# usb-power-maker.net
KiCad netlist of a schematic drawn in EAGLE
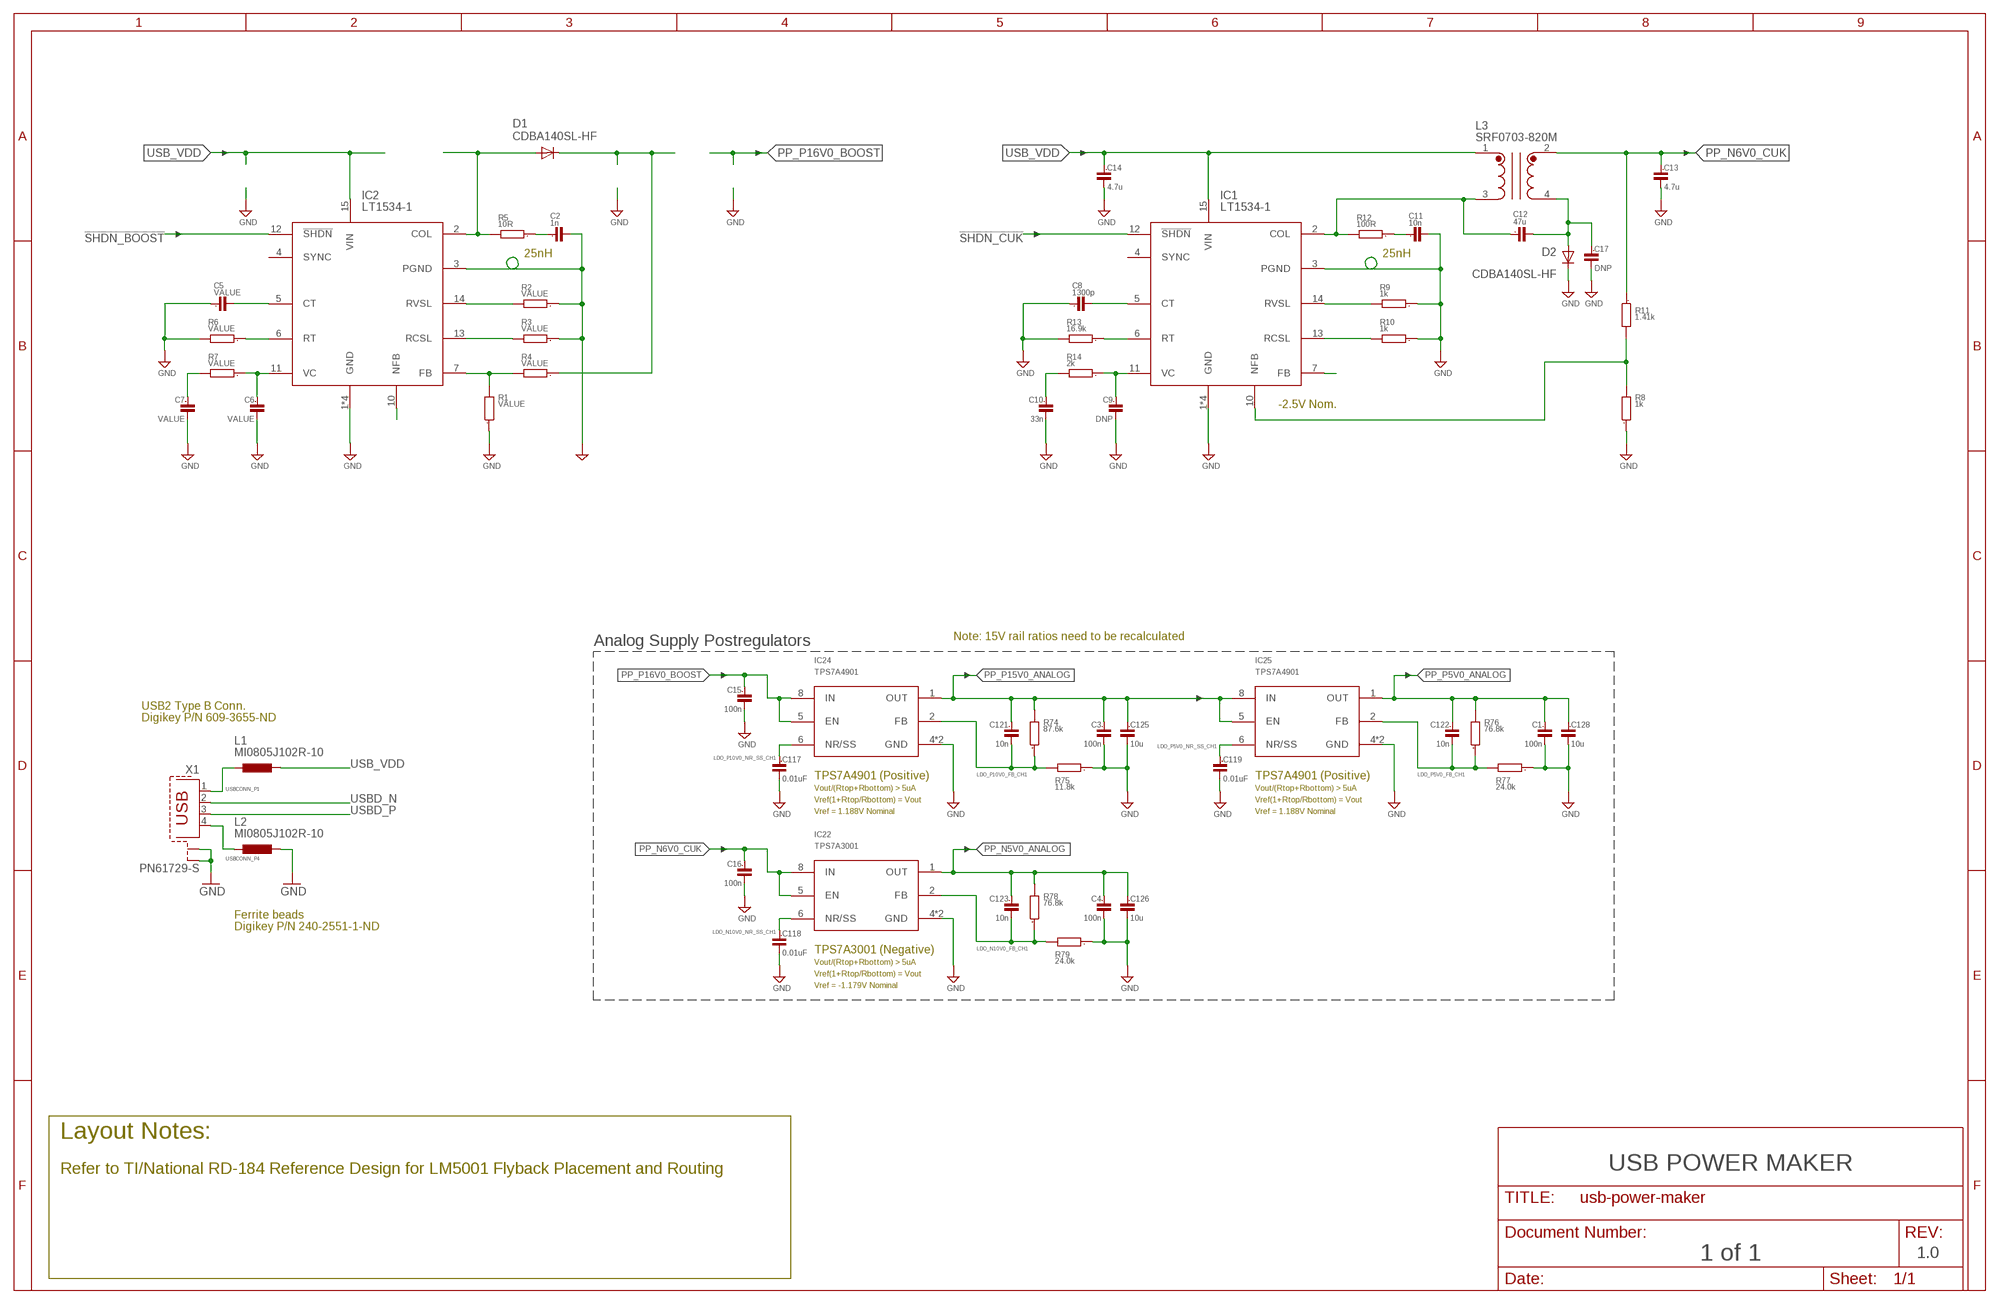
[diagram p0: schematic, sheet 1]

(export (version "E")
  (design (tool "Eeschema 10.0.6"))
  (components
    (comp (ref "C1")
      (value "100n")
      (footprint "eagle-import:0603")
      (libsource (lib "eagle-import") (part "C0603"))
    )
    (comp (ref "C2")
      (value "1n")
      (footprint "eagle-import:0603")
      (libsource (lib "eagle-import") (part "C0603"))
    )
    (comp (ref "C3")
      (value "100n")
      (footprint "eagle-import:0603")
      (libsource (lib "eagle-import") (part "C0603"))
    )
    (comp (ref "C4")
      (value "100n")
      (footprint "eagle-import:0603")
      (libsource (lib "eagle-import") (part "C0603"))
    )
    (comp (ref "C5")
      (value "VALUE")
      (footprint "eagle-import:0603")
      (libsource (lib "eagle-import") (part "C0603"))
    )
    (comp (ref "C6")
      (value "VALUE")
      (footprint "eagle-import:0603")
      (libsource (lib "eagle-import") (part "C0603"))
    )
    (comp (ref "C7")
      (value "VALUE")
      (footprint "eagle-import:0603")
      (libsource (lib "eagle-import") (part "C0603"))
    )
    (comp (ref "C8")
      (value "1300p")
      (footprint "eagle-import:0603")
      (libsource (lib "eagle-import") (part "C0603"))
    )
    (comp (ref "C9")
      (value "DNP")
      (footprint "eagle-import:0603")
      (libsource (lib "eagle-import") (part "C0603"))
    )
    (comp (ref "C10")
      (value "33n")
      (footprint "eagle-import:0603")
      (libsource (lib "eagle-import") (part "C0603"))
    )
    (comp (ref "C11")
      (value "10n")
      (footprint "eagle-import:0603")
      (libsource (lib "eagle-import") (part "C0603"))
    )
    (comp (ref "C12")
      (value "47u")
      (footprint "eagle-import:0805")
      (libsource (lib "eagle-import") (part "C0805"))
    )
    (comp (ref "C13")
      (value "4.7u")
      (footprint "eagle-import:0805")
      (libsource (lib "eagle-import") (part "C0805"))
    )
    (comp (ref "C14")
      (value "4.7u")
      (footprint "eagle-import:0805")
      (libsource (lib "eagle-import") (part "C0805"))
    )
    (comp (ref "C15")
      (value "100n")
      (footprint "eagle-import:0603")
      (libsource (lib "eagle-import") (part "C0603"))
    )
    (comp (ref "C16")
      (value "100n")
      (footprint "eagle-import:0603")
      (libsource (lib "eagle-import") (part "C0603"))
    )
    (comp (ref "C17")
      (value "DNP")
      (footprint "eagle-import:0603")
      (libsource (lib "eagle-import") (part "C0603"))
    )
    (comp (ref "C117")
      (value "0.01uF")
      (footprint "eagle-import:0603")
      (libsource (lib "eagle-import") (part "C0603"))
    )
    (comp (ref "C118")
      (value "0.01uF")
      (footprint "eagle-import:0603")
      (libsource (lib "eagle-import") (part "C0603"))
    )
    (comp (ref "C119")
      (value "0.01uF")
      (footprint "eagle-import:0603")
      (libsource (lib "eagle-import") (part "C0603"))
    )
    (comp (ref "C121")
      (value "10n")
      (footprint "eagle-import:0603")
      (libsource (lib "eagle-import") (part "C0603"))
    )
    (comp (ref "C122")
      (value "10n")
      (footprint "eagle-import:0603")
      (libsource (lib "eagle-import") (part "C0603"))
    )
    (comp (ref "C123")
      (value "10n")
      (footprint "eagle-import:0603")
      (libsource (lib "eagle-import") (part "C0603"))
    )
    (comp (ref "C125")
      (value "10u")
      (footprint "eagle-import:0805")
      (libsource (lib "eagle-import") (part "C0805"))
    )
    (comp (ref "C126")
      (value "10u")
      (footprint "eagle-import:0805")
      (libsource (lib "eagle-import") (part "C0805"))
    )
    (comp (ref "C128")
      (value "10u")
      (footprint "eagle-import:0805")
      (libsource (lib "eagle-import") (part "C0805"))
    )
    (comp (ref "D1")
      (value "CDBA140SL-HF")
      (footprint "eagle-import:DO214AC")
      (libsource (lib "eagle-import") (part "DIODE-DO214AC"))
    )
    (comp (ref "D2")
      (value "CDBA140SL-HF")
      (footprint "eagle-import:DO214AC")
      (libsource (lib "eagle-import") (part "DIODE-DO214AC"))
    )
    (comp (ref "IC1")
      (value "LT1534-1")
      (footprint "eagle-import:SO16")
      (libsource (lib "eagle-import") (part "LT1534"))
    )
    (comp (ref "IC2")
      (value "LT1534-1")
      (footprint "eagle-import:SO16")
      (libsource (lib "eagle-import") (part "LT1534"))
    )
    (comp (ref "IC22")
      (value "TPS7A3001")
      (footprint "eagle-import:MSOP-8_POWER_PAD")
      (libsource (lib "eagle-import") (part "TPS7A"))
    )
    (comp (ref "IC24")
      (value "TPS7A4901")
      (footprint "eagle-import:MSOP-8_POWER_PAD")
      (libsource (lib "eagle-import") (part "TPS7A"))
    )
    (comp (ref "IC25")
      (value "TPS7A4901")
      (footprint "eagle-import:MSOP-8_POWER_PAD")
      (libsource (lib "eagle-import") (part "TPS7A"))
    )
    (comp (ref "L1")
      (value "MI0805J102R-10")
      (footprint "eagle-import:R0805")
      (libsource (lib "eagle-import") (part "INDUCTOR0805"))
    )
    (comp (ref "L2")
      (value "MI0805J102R-10")
      (footprint "eagle-import:R0805")
      (libsource (lib "eagle-import") (part "INDUCTOR0805"))
    )
    (comp (ref "L3")
      (value "SRF0703-820M")
      (footprint "eagle-import:SRF0703")
      (libsource (lib "eagle-import") (part "SRF0703"))
    )
    (comp (ref "R1")
      (value "VALUE")
      (footprint "eagle-import:0603")
      (libsource (lib "eagle-import") (part "R0603"))
    )
    (comp (ref "R2")
      (value "VALUE")
      (footprint "eagle-import:0603")
      (libsource (lib "eagle-import") (part "R0603"))
    )
    (comp (ref "R3")
      (value "VALUE")
      (footprint "eagle-import:0603")
      (libsource (lib "eagle-import") (part "R0603"))
    )
    (comp (ref "R4")
      (value "VALUE")
      (footprint "eagle-import:0603")
      (libsource (lib "eagle-import") (part "R0603"))
    )
    (comp (ref "R5")
      (value "10R")
      (footprint "eagle-import:0603")
      (libsource (lib "eagle-import") (part "R0603"))
    )
    (comp (ref "R6")
      (value "VALUE")
      (footprint "eagle-import:0603")
      (libsource (lib "eagle-import") (part "R0603"))
    )
    (comp (ref "R7")
      (value "VALUE")
      (footprint "eagle-import:0603")
      (libsource (lib "eagle-import") (part "R0603"))
    )
    (comp (ref "R8")
      (value "1k")
      (footprint "eagle-import:0603")
      (libsource (lib "eagle-import") (part "R0603"))
    )
    (comp (ref "R9")
      (value "1k")
      (footprint "eagle-import:0603")
      (libsource (lib "eagle-import") (part "R0603"))
    )
    (comp (ref "R10")
      (value "1k")
      (footprint "eagle-import:0603")
      (libsource (lib "eagle-import") (part "R0603"))
    )
    (comp (ref "R11")
      (value "1.41k")
      (footprint "eagle-import:0603")
      (libsource (lib "eagle-import") (part "R0603"))
    )
    (comp (ref "R12")
      (value "100R")
      (footprint "eagle-import:0603")
      (libsource (lib "eagle-import") (part "R0603"))
    )
    (comp (ref "R13")
      (value "16.9k")
      (footprint "eagle-import:0603")
      (libsource (lib "eagle-import") (part "R0603"))
    )
    (comp (ref "R14")
      (value "2k")
      (footprint "eagle-import:0603")
      (libsource (lib "eagle-import") (part "R0603"))
    )
    (comp (ref "R74")
      (value "87.6k")
      (footprint "eagle-import:0603")
      (libsource (lib "eagle-import") (part "R0603"))
    )
    (comp (ref "R75")
      (value "11.8k")
      (footprint "eagle-import:0603")
      (libsource (lib "eagle-import") (part "R0603"))
    )
    (comp (ref "R76")
      (value "76.8k")
      (footprint "eagle-import:0603")
      (libsource (lib "eagle-import") (part "R0603"))
    )
    (comp (ref "R77")
      (value "24.0k")
      (footprint "eagle-import:0603")
      (libsource (lib "eagle-import") (part "R0603"))
    )
    (comp (ref "R78")
      (value "76.8k")
      (footprint "eagle-import:0603")
      (libsource (lib "eagle-import") (part "R0603"))
    )
    (comp (ref "R79")
      (value "24.0k")
      (footprint "eagle-import:0603")
      (libsource (lib "eagle-import") (part "R0603"))
    )
    (comp (ref "X1")
      (value "PN61729-S")
      (footprint "eagle-import:PN61729-S")
      (libsource (lib "eagle-import") (part "PN61729-S"))
    )
  )
  (nets
    (net (code "1") (name "/LDO_N10V0_FB_CH1") (class "Default")
      (node (ref "C123") (pin "2") (pinfunction "2_2") (pintype "passive"))
      (node (ref "IC22") (pin "2") (pinfunction "FB_2") (pintype "bidirectional"))
      (node (ref "R78") (pin "1") (pinfunction "1_1") (pintype "passive"))
      (node (ref "R79") (pin "2") (pinfunction "2_2") (pintype "passive"))
    )
    (net (code "2") (name "/LDO_N10V0_NR_SS_CH1") (class "Default")
      (node (ref "C118") (pin "1") (pinfunction "1_1") (pintype "passive"))
      (node (ref "IC22") (pin "6") (pinfunction "NR/SS_6") (pintype "bidirectional"))
    )
    (net (code "3") (name "/LDO_P5V0_FB_CH1") (class "Default")
      (node (ref "C122") (pin "2") (pinfunction "2_2") (pintype "passive"))
      (node (ref "IC25") (pin "2") (pinfunction "FB_2") (pintype "bidirectional"))
      (node (ref "R76") (pin "1") (pinfunction "1_1") (pintype "passive"))
      (node (ref "R77") (pin "2") (pinfunction "2_2") (pintype "passive"))
    )
    (net (code "4") (name "/LDO_P5V0_NR_SS_CH1") (class "Default")
      (node (ref "C119") (pin "1") (pinfunction "1_1") (pintype "passive"))
      (node (ref "IC25") (pin "6") (pinfunction "NR/SS_6") (pintype "bidirectional"))
    )
    (net (code "5") (name "/LDO_P10V0_FB_CH1") (class "Default")
      (node (ref "C121") (pin "2") (pinfunction "2_2") (pintype "passive"))
      (node (ref "IC24") (pin "2") (pinfunction "FB_2") (pintype "bidirectional"))
      (node (ref "R74") (pin "1") (pinfunction "1_1") (pintype "passive"))
      (node (ref "R75") (pin "2") (pinfunction "2_2") (pintype "passive"))
    )
    (net (code "6") (name "/LDO_P10V0_NR_SS_CH1") (class "Default")
      (node (ref "C117") (pin "1") (pinfunction "1_1") (pintype "passive"))
      (node (ref "IC24") (pin "6") (pinfunction "NR/SS_6") (pintype "bidirectional"))
    )
    (net (code "7") (name "/USBCONN_P1") (class "Default")
      (node (ref "L1") (pin "1") (pinfunction "P$1_1") (pintype "bidirectional"))
      (node (ref "X1") (pin "1") (pinfunction "1_1") (pintype "passive"))
    )
    (net (code "8") (name "/USBCONN_P4") (class "Default")
      (node (ref "L2") (pin "1") (pinfunction "P$1_1") (pintype "bidirectional"))
      (node (ref "X1") (pin "4") (pinfunction "4_4") (pintype "passive"))
    )
    (net (code "9") (name "/USBD_N") (class "Default")
      (node (ref "X1") (pin "2") (pinfunction "2_2") (pintype "passive"))
    )
    (net (code "10") (name "/USBD_P") (class "Default")
      (node (ref "X1") (pin "3") (pinfunction "3_3") (pintype "passive"))
    )
    (net (code "11") (name "/~{SHDN_BOOST}") (class "Default")
      (node (ref "IC2") (pin "12") (pinfunction "~{SHDN}_12") (pintype "bidirectional"))
    )
    (net (code "12") (name "/~{SHDN_CUK}") (class "Default")
      (node (ref "IC1") (pin "12") (pinfunction "~{SHDN}_12") (pintype "bidirectional"))
    )
    (net (code "13") (name "GND") (class "Default")
      (node (ref "C1") (pin "2") (pinfunction "2_2") (pintype "passive"))
      (node (ref "C10") (pin "2") (pinfunction "2_2") (pintype "passive"))
      (node (ref "C11") (pin "2") (pinfunction "2_2") (pintype "passive"))
      (node (ref "C117") (pin "2") (pinfunction "2_2") (pintype "passive"))
      (node (ref "C118") (pin "2") (pinfunction "2_2") (pintype "passive"))
      (node (ref "C119") (pin "2") (pinfunction "2_2") (pintype "passive"))
      (node (ref "C125") (pin "2") (pinfunction "2_2") (pintype "passive"))
      (node (ref "C126") (pin "2") (pinfunction "2_2") (pintype "passive"))
      (node (ref "C128") (pin "2") (pinfunction "2_2") (pintype "passive"))
      (node (ref "C13") (pin "2") (pinfunction "2_2") (pintype "passive"))
      (node (ref "C14") (pin "2") (pinfunction "2_2") (pintype "passive"))
      (node (ref "C15") (pin "2") (pinfunction "2_2") (pintype "passive"))
      (node (ref "C16") (pin "2") (pinfunction "2_2") (pintype "passive"))
      (node (ref "C17") (pin "2") (pinfunction "2_2") (pintype "passive"))
      (node (ref "C2") (pin "2") (pinfunction "2_2") (pintype "passive"))
      (node (ref "C3") (pin "2") (pinfunction "2_2") (pintype "passive"))
      (node (ref "C4") (pin "2") (pinfunction "2_2") (pintype "passive"))
      (node (ref "C5") (pin "1") (pinfunction "1_1") (pintype "passive"))
      (node (ref "C6") (pin "2") (pinfunction "2_2") (pintype "passive"))
      (node (ref "C7") (pin "2") (pinfunction "2_2") (pintype "passive"))
      (node (ref "C8") (pin "1") (pinfunction "1_1") (pintype "passive"))
      (node (ref "C9") (pin "2") (pinfunction "2_2") (pintype "passive"))
      (node (ref "D2") (pin "C") (pinfunction "C_C") (pintype "passive"))
      (node (ref "IC1") (pin "1") (pinfunction "GND_1") (pintype "bidirectional"))
      (node (ref "IC1") (pin "16") (pinfunction "GND_16") (pintype "bidirectional"))
      (node (ref "IC1") (pin "3") (pinfunction "PGND_3") (pintype "bidirectional"))
      (node (ref "IC1") (pin "8") (pinfunction "GND_8") (pintype "bidirectional"))
      (node (ref "IC1") (pin "9") (pinfunction "GND_9") (pintype "bidirectional"))
      (node (ref "IC2") (pin "1") (pinfunction "GND_1") (pintype "bidirectional"))
      (node (ref "IC2") (pin "16") (pinfunction "GND_16") (pintype "bidirectional"))
      (node (ref "IC2") (pin "3") (pinfunction "PGND_3") (pintype "bidirectional"))
      (node (ref "IC2") (pin "8") (pinfunction "GND_8") (pintype "bidirectional"))
      (node (ref "IC2") (pin "9") (pinfunction "GND_9") (pintype "bidirectional"))
      (node (ref "IC22") (pin "4") (pinfunction "GND_4") (pintype "bidirectional"))
      (node (ref "IC22") (pin "PAD") (pinfunction "GND_PAD") (pintype "bidirectional"))
      (node (ref "IC24") (pin "4") (pinfunction "GND_4") (pintype "bidirectional"))
      (node (ref "IC24") (pin "PAD") (pinfunction "GND_PAD") (pintype "bidirectional"))
      (node (ref "IC25") (pin "4") (pinfunction "GND_4") (pintype "bidirectional"))
      (node (ref "IC25") (pin "PAD") (pinfunction "GND_PAD") (pintype "bidirectional"))
      (node (ref "L2") (pin "2") (pinfunction "P$2_2") (pintype "bidirectional"))
      (node (ref "R1") (pin "1") (pinfunction "1_1") (pintype "passive"))
      (node (ref "R10") (pin "1") (pinfunction "1_1") (pintype "passive"))
      (node (ref "R13") (pin "2") (pinfunction "2_2") (pintype "passive"))
      (node (ref "R2") (pin "1") (pinfunction "1_1") (pintype "passive"))
      (node (ref "R3") (pin "1") (pinfunction "1_1") (pintype "passive"))
      (node (ref "R6") (pin "2") (pinfunction "2_2") (pintype "passive"))
      (node (ref "R75") (pin "1") (pinfunction "1_1") (pintype "passive"))
      (node (ref "R77") (pin "1") (pinfunction "1_1") (pintype "passive"))
      (node (ref "R79") (pin "1") (pinfunction "1_1") (pintype "passive"))
      (node (ref "R8") (pin "1") (pinfunction "1_1") (pintype "passive"))
      (node (ref "R9") (pin "1") (pinfunction "1_1") (pintype "passive"))
      (node (ref "X1") (pin "S1") (pinfunction "S1_S1") (pintype "passive"))
      (node (ref "X1") (pin "S2") (pinfunction "S2_S2") (pintype "passive"))
    )
    (net (code "14") (name "Net-(C2-Pad1)") (class "Default")
      (node (ref "C2") (pin "1") (pinfunction "1_1") (pintype "passive"))
      (node (ref "R5") (pin "1") (pinfunction "1_1") (pintype "passive"))
    )
    (net (code "15") (name "Net-(C7-Pad1)") (class "Default")
      (node (ref "C7") (pin "1") (pinfunction "1_1") (pintype "passive"))
      (node (ref "R7") (pin "2") (pinfunction "2_2") (pintype "passive"))
    )
    (net (code "16") (name "Net-(C10-Pad1)") (class "Default")
      (node (ref "C10") (pin "1") (pinfunction "1_1") (pintype "passive"))
      (node (ref "R14") (pin "2") (pinfunction "2_2") (pintype "passive"))
    )
    (net (code "17") (name "Net-(C11-Pad1)") (class "Default")
      (node (ref "C11") (pin "1") (pinfunction "1_1") (pintype "passive"))
      (node (ref "R12") (pin "1") (pinfunction "1_1") (pintype "passive"))
    )
    (net (code "18") (name "Net-(C12-Pad2)") (class "Default")
      (node (ref "C12") (pin "2") (pinfunction "2_2") (pintype "passive"))
      (node (ref "C17") (pin "1") (pinfunction "1_1") (pintype "passive"))
      (node (ref "D2") (pin "A") (pinfunction "A_A") (pintype "passive"))
      (node (ref "L3") (pin "4") (pinfunction "4_4") (pintype "bidirectional"))
    )
    (net (code "19") (name "Net-(D1-PadC)") (class "Default")
      (node (ref "D1") (pin "C") (pinfunction "C_C") (pintype "passive"))
      (node (ref "R4") (pin "1") (pinfunction "1_1") (pintype "passive"))
    )
    (net (code "20") (name "Net-(IC1-COL)") (class "Default")
      (node (ref "C12") (pin "1") (pinfunction "1_1") (pintype "passive"))
      (node (ref "IC1") (pin "2") (pinfunction "COL_2") (pintype "bidirectional"))
      (node (ref "L3") (pin "3") (pinfunction "3_3") (pintype "bidirectional"))
      (node (ref "R12") (pin "2") (pinfunction "2_2") (pintype "passive"))
    )
    (net (code "21") (name "Net-(IC1-CT)") (class "Default")
      (node (ref "C8") (pin "2") (pinfunction "2_2") (pintype "passive"))
      (node (ref "IC1") (pin "5") (pinfunction "CT_5") (pintype "bidirectional"))
    )
    (net (code "22") (name "Net-(IC1-NFB)") (class "Default")
      (node (ref "IC1") (pin "10") (pinfunction "NFB_10") (pintype "bidirectional"))
      (node (ref "R11") (pin "2") (pinfunction "2_2") (pintype "passive"))
      (node (ref "R8") (pin "2") (pinfunction "2_2") (pintype "passive"))
    )
    (net (code "23") (name "Net-(IC1-RCSL)") (class "Default")
      (node (ref "IC1") (pin "13") (pinfunction "RCSL_13") (pintype "bidirectional"))
      (node (ref "R10") (pin "2") (pinfunction "2_2") (pintype "passive"))
    )
    (net (code "24") (name "Net-(IC1-RT)") (class "Default")
      (node (ref "IC1") (pin "6") (pinfunction "RT_6") (pintype "bidirectional"))
      (node (ref "R13") (pin "1") (pinfunction "1_1") (pintype "passive"))
    )
    (net (code "25") (name "Net-(IC1-RVSL)") (class "Default")
      (node (ref "IC1") (pin "14") (pinfunction "RVSL_14") (pintype "bidirectional"))
      (node (ref "R9") (pin "2") (pinfunction "2_2") (pintype "passive"))
    )
    (net (code "26") (name "Net-(IC1-VC)") (class "Default")
      (node (ref "C9") (pin "1") (pinfunction "1_1") (pintype "passive"))
      (node (ref "IC1") (pin "11") (pinfunction "VC_11") (pintype "bidirectional"))
      (node (ref "R14") (pin "1") (pinfunction "1_1") (pintype "passive"))
    )
    (net (code "27") (name "Net-(IC2-COL)") (class "Default")
      (node (ref "D1") (pin "A") (pinfunction "A_A") (pintype "passive"))
      (node (ref "IC2") (pin "2") (pinfunction "COL_2") (pintype "bidirectional"))
      (node (ref "R5") (pin "2") (pinfunction "2_2") (pintype "passive"))
    )
    (net (code "28") (name "Net-(IC2-CT)") (class "Default")
      (node (ref "C5") (pin "2") (pinfunction "2_2") (pintype "passive"))
      (node (ref "IC2") (pin "5") (pinfunction "CT_5") (pintype "bidirectional"))
    )
    (net (code "29") (name "Net-(IC2-FB)") (class "Default")
      (node (ref "IC2") (pin "7") (pinfunction "FB_7") (pintype "bidirectional"))
      (node (ref "R1") (pin "2") (pinfunction "2_2") (pintype "passive"))
      (node (ref "R4") (pin "2") (pinfunction "2_2") (pintype "passive"))
    )
    (net (code "30") (name "Net-(IC2-RCSL)") (class "Default")
      (node (ref "IC2") (pin "13") (pinfunction "RCSL_13") (pintype "bidirectional"))
      (node (ref "R3") (pin "2") (pinfunction "2_2") (pintype "passive"))
    )
    (net (code "31") (name "Net-(IC2-RT)") (class "Default")
      (node (ref "IC2") (pin "6") (pinfunction "RT_6") (pintype "bidirectional"))
      (node (ref "R6") (pin "1") (pinfunction "1_1") (pintype "passive"))
    )
    (net (code "32") (name "Net-(IC2-RVSL)") (class "Default")
      (node (ref "IC2") (pin "14") (pinfunction "RVSL_14") (pintype "bidirectional"))
      (node (ref "R2") (pin "2") (pinfunction "2_2") (pintype "passive"))
    )
    (net (code "33") (name "Net-(IC2-VC)") (class "Default")
      (node (ref "C6") (pin "1") (pinfunction "1_1") (pintype "passive"))
      (node (ref "IC2") (pin "11") (pinfunction "VC_11") (pintype "bidirectional"))
      (node (ref "R7") (pin "1") (pinfunction "1_1") (pintype "passive"))
    )
    (net (code "34") (name "PP_N5V0_ANALOG") (class "Default")
      (node (ref "C123") (pin "1") (pinfunction "1_1") (pintype "passive"))
      (node (ref "C126") (pin "1") (pinfunction "1_1") (pintype "passive"))
      (node (ref "C4") (pin "1") (pinfunction "1_1") (pintype "passive"))
      (node (ref "IC22") (pin "1") (pinfunction "OUT_1") (pintype "bidirectional"))
      (node (ref "R78") (pin "2") (pinfunction "2_2") (pintype "passive"))
    )
    (net (code "35") (name "PP_N6V0_CUK") (class "Default")
      (node (ref "C13") (pin "1") (pinfunction "1_1") (pintype "passive"))
      (node (ref "C16") (pin "1") (pinfunction "1_1") (pintype "passive"))
      (node (ref "IC22") (pin "5") (pinfunction "EN_5") (pintype "bidirectional"))
      (node (ref "IC22") (pin "8") (pinfunction "IN_8") (pintype "bidirectional"))
      (node (ref "L3") (pin "2") (pinfunction "2_2") (pintype "bidirectional"))
      (node (ref "R11") (pin "1") (pinfunction "1_1") (pintype "passive"))
    )
    (net (code "36") (name "PP_P5V0_ANALOG") (class "Default")
      (node (ref "C1") (pin "1") (pinfunction "1_1") (pintype "passive"))
      (node (ref "C122") (pin "1") (pinfunction "1_1") (pintype "passive"))
      (node (ref "C128") (pin "1") (pinfunction "1_1") (pintype "passive"))
      (node (ref "IC25") (pin "1") (pinfunction "OUT_1") (pintype "bidirectional"))
      (node (ref "R76") (pin "2") (pinfunction "2_2") (pintype "passive"))
    )
    (net (code "37") (name "PP_P15V0_ANALOG") (class "Default")
      (node (ref "C121") (pin "1") (pinfunction "1_1") (pintype "passive"))
      (node (ref "C125") (pin "1") (pinfunction "1_1") (pintype "passive"))
      (node (ref "C3") (pin "1") (pinfunction "1_1") (pintype "passive"))
      (node (ref "IC24") (pin "1") (pinfunction "OUT_1") (pintype "bidirectional"))
      (node (ref "IC25") (pin "5") (pinfunction "EN_5") (pintype "bidirectional"))
      (node (ref "IC25") (pin "8") (pinfunction "IN_8") (pintype "bidirectional"))
      (node (ref "R74") (pin "2") (pinfunction "2_2") (pintype "passive"))
    )
    (net (code "38") (name "PP_P16V0_BOOST") (class "Default")
      (node (ref "C15") (pin "1") (pinfunction "1_1") (pintype "passive"))
      (node (ref "IC24") (pin "5") (pinfunction "EN_5") (pintype "bidirectional"))
      (node (ref "IC24") (pin "8") (pinfunction "IN_8") (pintype "bidirectional"))
    )
    (net (code "39") (name "USB_VDD") (class "Default")
      (node (ref "C14") (pin "1") (pinfunction "1_1") (pintype "passive"))
      (node (ref "IC1") (pin "15") (pinfunction "VIN_15") (pintype "bidirectional"))
      (node (ref "IC2") (pin "15") (pinfunction "VIN_15") (pintype "bidirectional"))
      (node (ref "L1") (pin "2") (pinfunction "P$2_2") (pintype "bidirectional"))
      (node (ref "L3") (pin "1") (pinfunction "1_1") (pintype "bidirectional"))
    )
    (net (code "40") (name "unconnected-(IC1-FB-Pad7)") (class "Default")
      (node (ref "IC1") (pin "7") (pinfunction "FB_7") (pintype "bidirectional"))
    )
    (net (code "41") (name "unconnected-(IC1-SYNC-Pad4)") (class "Default")
      (node (ref "IC1") (pin "4") (pinfunction "SYNC_4") (pintype "bidirectional"))
    )
    (net (code "42") (name "unconnected-(IC2-NFB-Pad10)") (class "Default")
      (node (ref "IC2") (pin "10") (pinfunction "NFB_10") (pintype "bidirectional"))
    )
    (net (code "43") (name "unconnected-(IC2-SYNC-Pad4)") (class "Default")
      (node (ref "IC2") (pin "4") (pinfunction "SYNC_4") (pintype "bidirectional"))
    )
  )
)
